# ZF.net
KiCad netlist of a schematic drawn in Altium Designer
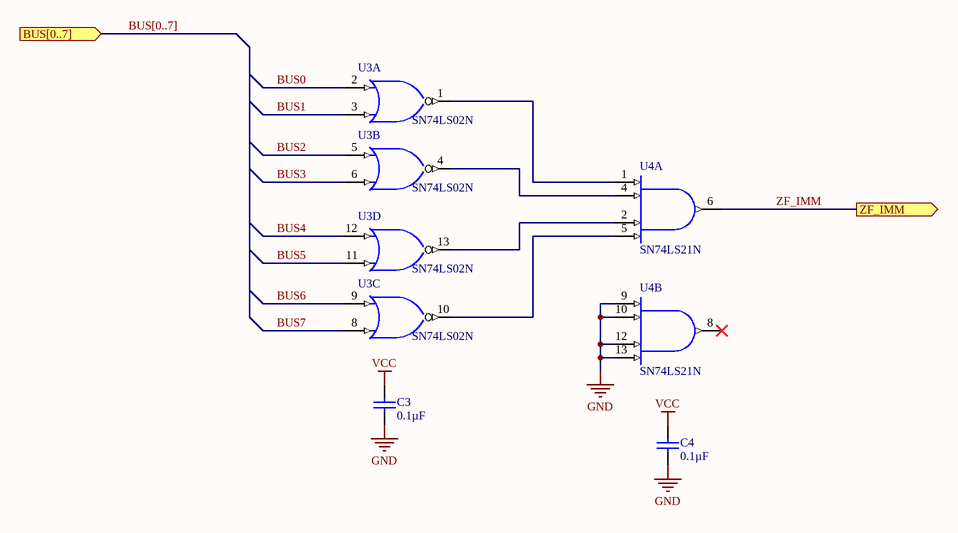
[diagram p0: ZF.SchDoc]

(export (version "E")
  (design (tool "Eeschema 10.0.6"))
  (components
    (comp (ref "C3")
      (value "K104K15X7RF5TL2")
      (footprint "VISH-K104K15X7RF5TL2")
      (description "Ceramic Capacitor, 100 nF, +/- 10%, 50 V, -55 to 125 degC, 2-Pin THD, RoHS, Tape and Reel")
      (fields
        (field (name "MANUFACTURER") "Vishay")
        (field (name "TOLERANCE") "±10%")
        (field (name "CAPACITANCE") "0.1µF")
      )
      (libsource (lib "Altium Content Vault") (part "CAP-NP-2"))
    )
    (comp (ref "C4")
      (value "K104K15X7RF5TL2")
      (footprint "VISH-K104K15X7RF5TL2")
      (description "Ceramic Capacitor, 100 nF, +/- 10%, 50 V, -55 to 125 degC, 2-Pin THD, RoHS, Tape and Reel")
      (fields
        (field (name "MANUFACTURER") "Vishay")
        (field (name "TOLERANCE") "±10%")
        (field (name "CAPACITANCE") "0.1µF")
      )
      (libsource (lib "Altium Content Vault") (part "CAP-NP-2"))
    )
    (comp (ref "U3")
      (value "SN74LS02N")
      (footprint "N014")
      (description "Quadruple 2-Input Positive-NOR Gate")
      (fields (field (name "PUBLISHER") "Altium Limited"))
      (libsource (lib "") (part "SN74LS02N_2"))
    )
    (comp (ref "U4")
      (value "SN74LS21N")
      (footprint "N014")
      (description "Dual 4-Input Positive-AND Gate")
      (fields (field (name "PUBLISHER") "Altium Limited"))
      (libsource (lib "") (part "SN74LS21N_1"))
    )
  )
  (nets
    (net (code "1") (name "/BUS0") (class "Default")
      (node (ref "U3") (pin "2") (pinfunction "A_2") (pintype "input"))
    )
    (net (code "2") (name "/BUS1") (class "Default")
      (node (ref "U3") (pin "3") (pinfunction "B_3") (pintype "input"))
    )
    (net (code "3") (name "/BUS2") (class "Default")
      (node (ref "U3") (pin "5") (pinfunction "A_5") (pintype "input"))
    )
    (net (code "4") (name "/BUS3") (class "Default")
      (node (ref "U3") (pin "6") (pinfunction "B_6") (pintype "input"))
    )
    (net (code "5") (name "/BUS4") (class "Default")
      (node (ref "U3") (pin "12") (pinfunction "B_12") (pintype "input"))
    )
    (net (code "6") (name "/BUS5") (class "Default")
      (node (ref "U3") (pin "11") (pinfunction "A_11") (pintype "input"))
    )
    (net (code "7") (name "/BUS6") (class "Default")
      (node (ref "U3") (pin "9") (pinfunction "B_9") (pintype "input"))
    )
    (net (code "8") (name "/BUS7") (class "Default")
      (node (ref "U3") (pin "8") (pinfunction "A_8") (pintype "input"))
    )
    (net (code "10") (name "/ZF_IMM") (class "Default")
      (node (ref "U4") (pin "6") (pinfunction "Y_6") (pintype "output"))
    )
    (net (code "11") (name "GND") (class "Default")
      (node (ref "C3") (pin "2") (pinfunction "2_2") (pintype "passive"))
      (node (ref "C4") (pin "2") (pinfunction "2_2") (pintype "passive"))
      (node (ref "U3") (pin "7") (pinfunction "GND_7") (pintype "power_in"))
      (node (ref "U4") (pin "10") (pinfunction "B_10") (pintype "input"))
      (node (ref "U4") (pin "12") (pinfunction "C_12") (pintype "input"))
      (node (ref "U4") (pin "13") (pinfunction "D_13") (pintype "input"))
      (node (ref "U4") (pin "7") (pinfunction "GND_7") (pintype "power_in"))
      (node (ref "U4") (pin "9") (pinfunction "A_9") (pintype "input"))
    )
    (net (code "12") (name "Net-(U3A-Y)") (class "Default")
      (node (ref "U3") (pin "1") (pinfunction "Y_1") (pintype "output"))
      (node (ref "U4") (pin "1") (pinfunction "A_1") (pintype "input"))
    )
    (net (code "13") (name "Net-(U3B-Y)") (class "Default")
      (node (ref "U3") (pin "4") (pinfunction "Y_4") (pintype "output"))
      (node (ref "U4") (pin "4") (pinfunction "C_4") (pintype "input"))
    )
    (net (code "14") (name "Net-(U3C-Y)") (class "Default")
      (node (ref "U3") (pin "10") (pinfunction "Y_10") (pintype "output"))
      (node (ref "U4") (pin "5") (pinfunction "D_5") (pintype "input"))
    )
    (net (code "15") (name "Net-(U3D-Y)") (class "Default")
      (node (ref "U3") (pin "13") (pinfunction "Y_13") (pintype "output"))
      (node (ref "U4") (pin "2") (pinfunction "B_2") (pintype "input"))
    )
    (net (code "16") (name "VCC") (class "Default")
      (node (ref "C3") (pin "1") (pinfunction "1_1") (pintype "passive"))
      (node (ref "C4") (pin "1") (pinfunction "1_1") (pintype "passive"))
      (node (ref "U3") (pin "14") (pinfunction "VCC_14") (pintype "power_in"))
      (node (ref "U4") (pin "14") (pinfunction "VCC_14") (pintype "power_in"))
    )
    (net (code "17") (name "unconnected-(U4B-Y-Pad8)") (class "Default")
      (node (ref "U4") (pin "8") (pinfunction "Y_8") (pintype "output+no_connect"))
    )
  )
)
